# tPen.net
KiCad netlist of a schematic drawn in Altium Designer
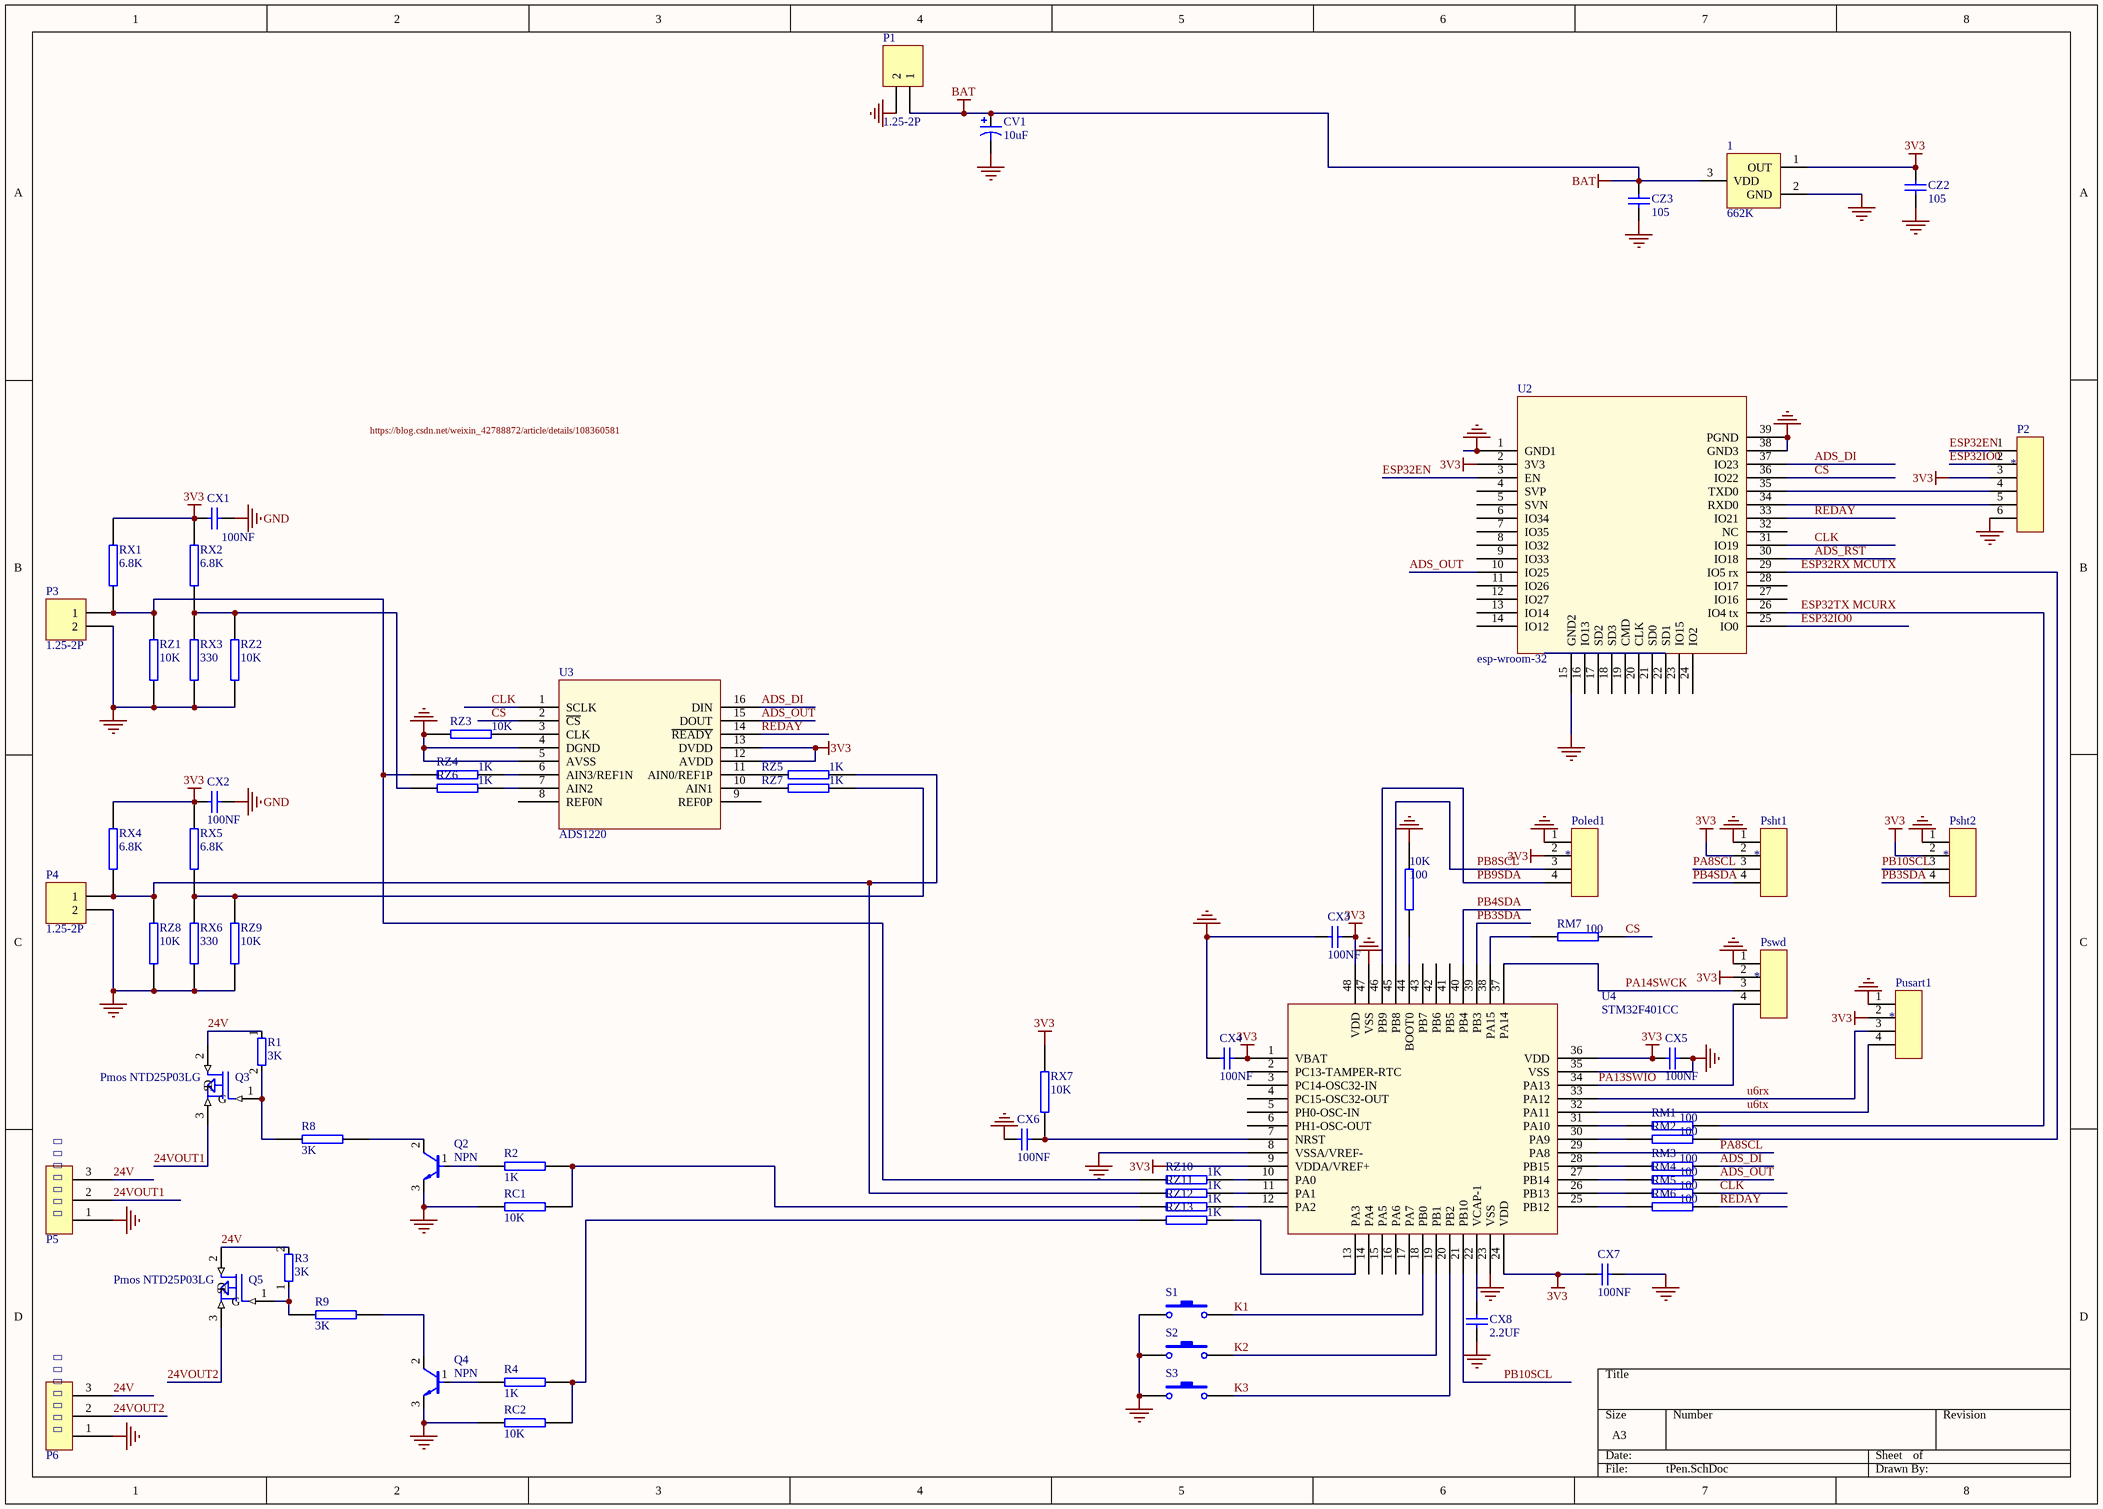
[diagram p0: tPen.SchDoc]

(export (version "E")
  (design (tool "Eeschema 10.0.6"))
  (components
    (comp (ref "1")
      (value "662K")
      (footprint "SOT23-3-1")
      (libsource (lib "SCHÔ­ï¿½ï¿½Í¼ï¿½ï¿½") (part "MH5330"))
    )
    (comp (ref "10K") (value "100") (footprint "0603") (libsource (lib "*") (part "RES2")))
    (comp (ref "CV1")
      (value "10uF")
      (footprint "0603")
      (description "Polarized Capacitor (Radial)")
      (libsource (lib "Miscellaneous Devices") (part "Cap Pol1"))
    )
    (comp (ref "CX1")
      (value "100NF")
      (footprint "0603")
      (description "Capacitor")
      (libsource (lib "Ô­ï¿½ï¿½Í¼ï¿½ï¿½") (part "104"))
    )
    (comp (ref "CX2")
      (value "100NF")
      (footprint "0603")
      (description "Capacitor")
      (libsource (lib "Ô­ï¿½ï¿½Í¼ï¿½ï¿½") (part "104"))
    )
    (comp (ref "CX3")
      (value "100NF")
      (footprint "0603")
      (description "Capacitor")
      (libsource (lib "Ô­ï¿½ï¿½Í¼ï¿½ï¿½") (part "104"))
    )
    (comp (ref "CX4")
      (value "100NF")
      (footprint "0603")
      (description "Capacitor")
      (libsource (lib "Ô­ï¿½ï¿½Í¼ï¿½ï¿½") (part "104"))
    )
    (comp (ref "CX5")
      (value "100NF")
      (footprint "0603")
      (description "Capacitor")
      (libsource (lib "Ô­ï¿½ï¿½Í¼ï¿½ï¿½") (part "104"))
    )
    (comp (ref "CX6")
      (value "100NF")
      (footprint "0603")
      (description "Capacitor")
      (libsource (lib "Ô­ï¿½ï¿½Í¼ï¿½ï¿½") (part "104"))
    )
    (comp (ref "CX7")
      (value "100NF")
      (footprint "0603")
      (description "Capacitor")
      (libsource (lib "Ô­ï¿½ï¿½Í¼ï¿½ï¿½") (part "104"))
    )
    (comp (ref "CX8")
      (value "2.2UF")
      (footprint "0603")
      (description "Capacitor")
      (libsource (lib "Ô­ï¿½ï¿½Í¼ï¿½ï¿½") (part "104"))
    )
    (comp (ref "CZ2")
      (value "105")
      (footprint "0603")
      (description "Capacitor")
      (libsource (lib "Ô­ï¿½ï¿½Í¼ï¿½ï¿½") (part "104"))
    )
    (comp (ref "CZ3")
      (value "105")
      (footprint "0603")
      (description "Capacitor")
      (libsource (lib "Ô­ï¿½ï¿½Í¼ï¿½ï¿½") (part "104"))
    )
    (comp (ref "P1")
      (value "1.25-2P")
      (footprint "1.25ï¿½ï¿½ï¿½ï¿½-ï¿½ï¿½Ê½Í¨ï¿½ï¿½-2P")
      (description "Header, 2-Pin")
      (fields (field (name "PUBLISHER") "Altium Limited"))
      (libsource (lib "") (part "Header 2_1"))
    )
    (comp (ref "P2") (value "*") (footprint "B6B-XH-A") (libsource (lib "") (part "ï¿½Ó²ï¿½ï¿½ï¿½ï¿?P_1")))
    (comp (ref "P3")
      (value "1.25-2P")
      (footprint "1.25ï¿½ï¿½ï¿½ï¿½-ï¿½ï¿½Ê½Í¨ï¿½ï¿½-2P")
      (description "Header, 2-Pin")
      (fields (field (name "PUBLISHER") "Altium Limited"))
      (libsource (lib "SCHÔ­ï¿½ï¿½Í¼ï¿½ï¿½") (part "Header 2"))
    )
    (comp (ref "P4")
      (value "1.25-2P")
      (footprint "1.25ï¿½ï¿½ï¿½ï¿½-ï¿½ï¿½Ê½Í¨ï¿½ï¿½-2P")
      (description "Header, 2-Pin")
      (fields (field (name "PUBLISHER") "Altium Limited"))
      (libsource (lib "SCHÔ­ï¿½ï¿½Í¼ï¿½ï¿½") (part "Header 2"))
    )
    (comp (ref "P5")
      (value "3Pï¿½ï¿½ï¿½ß¶ï¿½ï¿½ï¿½")
      (footprint "XH2.54-3")
      (libsource (lib "ï¿½Ó²ï¿½ï¿½Ôªï¿½ï¿½ï¿½ï¿?SchLib") (part "3Pï¿½ï¿½ï¿½ß¶ï¿½ï¿½ï¿½"))
    )
    (comp (ref "P6")
      (value "3Pï¿½ï¿½ï¿½ß¶ï¿½ï¿½ï¿½")
      (footprint "XH2.54-3")
      (libsource (lib "ï¿½Ó²ï¿½ï¿½Ôªï¿½ï¿½ï¿½ï¿?SchLib") (part "3Pï¿½ï¿½ï¿½ß¶ï¿½ï¿½ï¿½"))
    )
    (comp (ref "Poled1")
      (value "*")
      (footprint "0.96OLED")
      (libsource (lib "ï¿½Ó²ï¿½ï¿½Ôªï¿½ï¿½ï¿½ï¿?SchLib") (part "ï¿½Ó²ï¿½ï¿½ï¿½ï¿?P"))
    )
    (comp (ref "Psht1")
      (value "*")
      (footprint "B4B-XH-A")
      (libsource (lib "ï¿½Ó²ï¿½ï¿½Ôªï¿½ï¿½ï¿½ï¿?SchLib") (part "ï¿½Ó²ï¿½ï¿½ï¿½ï¿?P"))
    )
    (comp (ref "Psht2")
      (value "*")
      (footprint "B4B-XH-A")
      (libsource (lib "ï¿½Ó²ï¿½ï¿½Ôªï¿½ï¿½ï¿½ï¿?SchLib") (part "ï¿½Ó²ï¿½ï¿½ï¿½ï¿?P"))
    )
    (comp (ref "Pswd")
      (value "*")
      (footprint "B4B-XH-A")
      (libsource (lib "ï¿½Ó²ï¿½ï¿½Ôªï¿½ï¿½ï¿½ï¿?SchLib") (part "ï¿½Ó²ï¿½ï¿½ï¿½ï¿?P"))
    )
    (comp (ref "Pusart1")
      (value "*")
      (footprint "B4B-XH-A")
      (libsource (lib "ï¿½Ó²ï¿½ï¿½Ôªï¿½ï¿½ï¿½ï¿?SchLib") (part "ï¿½Ó²ï¿½ï¿½ï¿½ï¿?P"))
    )
    (comp (ref "Q2")
      (value "NPN")
      (footprint "SOT23")
      (libsource (lib "ï¿½ï¿½ï¿½ï¿½Ôªï¿½ï¿½ï¿½ï¿½") (part "NPN"))
    )
    (comp (ref "Q3")
      (value "Pmos NTD25P03LG")
      (libsource (lib "ï¿½ï¿½Ð§Ó¦ï¿½Ü¼ï¿½ï¿½É¿Ø¹ï¿½") (part "MOSFET P"))
    )
    (comp (ref "Q4")
      (value "NPN")
      (footprint "SOT23")
      (libsource (lib "ï¿½ï¿½ï¿½ï¿½Ôªï¿½ï¿½ï¿½ï¿½") (part "NPN"))
    )
    (comp (ref "Q5")
      (value "Pmos NTD25P03LG")
      (libsource (lib "ï¿½ï¿½Ð§Ó¦ï¿½Ü¼ï¿½ï¿½É¿Ø¹ï¿½") (part "MOSFET P"))
    )
    (comp (ref "R1") (value "3K") (footprint "0603") (libsource (lib "*") (part "RES")))
    (comp (ref "R2") (value "1K") (footprint "0603") (libsource (lib "*") (part "RES2")))
    (comp (ref "R3") (value "3K") (footprint "0603") (libsource (lib "*") (part "RES")))
    (comp (ref "R4") (value "1K") (footprint "0603") (libsource (lib "*") (part "RES2")))
    (comp (ref "R8") (value "3K") (footprint "0603") (libsource (lib "*") (part "RES2")))
    (comp (ref "R9") (value "3K") (footprint "0603") (libsource (lib "*") (part "RES2")))
    (comp (ref "RC1") (value "10K") (footprint "0603") (libsource (lib "*") (part "RES2")))
    (comp (ref "RC2") (value "10K") (footprint "0603") (libsource (lib "*") (part "RES2")))
    (comp (ref "RM1") (value "100") (footprint "0603") (libsource (lib "*") (part "RES2")))
    (comp (ref "RM2") (value "100") (footprint "0603") (libsource (lib "*") (part "RES2")))
    (comp (ref "RM3") (value "100") (footprint "0603") (libsource (lib "*") (part "RES2")))
    (comp (ref "RM4") (value "100") (footprint "0603") (libsource (lib "*") (part "RES2")))
    (comp (ref "RM5") (value "100") (footprint "0603") (libsource (lib "*") (part "RES2")))
    (comp (ref "RM6") (value "100") (footprint "0603") (libsource (lib "*") (part "RES2")))
    (comp (ref "RM7") (value "100") (footprint "0603") (libsource (lib "*") (part "RES2")))
    (comp (ref "RX1") (value "6.8K") (footprint "0603") (libsource (lib "*") (part "RES2")))
    (comp (ref "RX2") (value "6.8K") (footprint "0603") (libsource (lib "*") (part "RES2")))
    (comp (ref "RX3") (value "330") (footprint "0603") (libsource (lib "*") (part "RES2")))
    (comp (ref "RX4") (value "6.8K") (footprint "0603") (libsource (lib "*") (part "RES2")))
    (comp (ref "RX5") (value "6.8K") (footprint "0603") (libsource (lib "*") (part "RES2")))
    (comp (ref "RX6") (value "330") (footprint "0603") (libsource (lib "*") (part "RES2")))
    (comp (ref "RX7") (value "10K") (footprint "0603") (libsource (lib "*") (part "RES2")))
    (comp (ref "RZ1") (value "10K") (footprint "0603") (libsource (lib "*") (part "RES2")))
    (comp (ref "RZ2") (value "10K") (footprint "0603") (libsource (lib "*") (part "RES2")))
    (comp (ref "RZ3") (value "10K") (footprint "0603") (libsource (lib "*") (part "RES2")))
    (comp (ref "RZ4") (value "1K") (footprint "0603") (libsource (lib "*") (part "RES2")))
    (comp (ref "RZ5") (value "1K") (footprint "0603") (libsource (lib "*") (part "RES2")))
    (comp (ref "RZ6") (value "1K") (footprint "0603") (libsource (lib "*") (part "RES2")))
    (comp (ref "RZ7") (value "1K") (footprint "0603") (libsource (lib "*") (part "RES2")))
    (comp (ref "RZ8") (value "10K") (footprint "0603") (libsource (lib "*") (part "RES2")))
    (comp (ref "RZ9") (value "10K") (footprint "0603") (libsource (lib "*") (part "RES2")))
    (comp (ref "RZ10") (value "1K") (footprint "0603") (libsource (lib "*") (part "RES2")))
    (comp (ref "RZ11") (value "1K") (footprint "0603") (libsource (lib "*") (part "RES2")))
    (comp (ref "RZ12") (value "1K") (footprint "0603") (libsource (lib "*") (part "RES2")))
    (comp (ref "RZ13") (value "1K") (footprint "0603") (libsource (lib "*") (part "RES2")))
    (comp (ref "S1")
      (value "~")
      (footprint "ï¿½ï¿½Î»ï¿½ï¿½ï¿½ï¿½")
      (libsource (lib "ï¿½ï¿½ï¿½ï¿½_ï¿½ï¿½ï¿½ï¿½Ô­ï¿½ï¿½Í¼ï¿½ï¿½") (part "ï¿½á´¥ï¿½ï¿½ï¿½ï¿½"))
    )
    (comp (ref "S2")
      (value "~")
      (footprint "ï¿½ï¿½Î»ï¿½ï¿½ï¿½ï¿½")
      (libsource (lib "ï¿½ï¿½ï¿½ï¿½_ï¿½ï¿½ï¿½ï¿½Ô­ï¿½ï¿½Í¼ï¿½ï¿½") (part "ï¿½á´¥ï¿½ï¿½ï¿½ï¿½"))
    )
    (comp (ref "S3")
      (value "~")
      (footprint "ï¿½ï¿½Î»ï¿½ï¿½ï¿½ï¿½")
      (libsource (lib "ï¿½ï¿½ï¿½ï¿½_ï¿½ï¿½ï¿½ï¿½Ô­ï¿½ï¿½Í¼ï¿½ï¿½") (part "ï¿½á´¥ï¿½ï¿½ï¿½ï¿½"))
    )
    (comp (ref "U2")
      (value "esp-wroom-32")
      (footprint "ESP32")
      (libsource (lib "STM32F401CC") (part "esp-wroom-32"))
    )
    (comp (ref "U3") (value "ADS1220") (footprint "SSOP16") (libsource (lib "STM32F401CC") (part "ADS1220")))
    (comp (ref "U4")
      (value "STM32F401CC")
      (footprint "STM32F401CC-UFQFPN48")
      (libsource (lib "STM32F401CC") (part "STM32F401CC"))
    )
  )
  (nets
    (net (code "1") (name "/24V") (class "Default")
      (node (ref "P5") (pin "3") (pinfunction "3_3") (pintype "passive"))
      (node (ref "P6") (pin "3") (pinfunction "3_3") (pintype "passive"))
      (node (ref "Q3") (pin "2") (pinfunction "D_2") (pintype "input"))
      (node (ref "Q5") (pin "2") (pinfunction "D_2") (pintype "input"))
      (node (ref "R1") (pin "1") (pinfunction "1_1") (pintype "passive"))
      (node (ref "R3") (pin "2") (pinfunction "2_2") (pintype "passive"))
    )
    (net (code "2") (name "/24VOUT1") (class "Default")
      (node (ref "P5") (pin "2") (pinfunction "2_2") (pintype "passive"))
      (node (ref "Q3") (pin "3") (pinfunction "S_3") (pintype "input"))
    )
    (net (code "3") (name "/24VOUT2") (class "Default")
      (node (ref "P6") (pin "2") (pinfunction "2_2") (pintype "passive"))
      (node (ref "Q5") (pin "3") (pinfunction "S_3") (pintype "input"))
    )
    (net (code "4") (name "/ADS_DI") (class "Default")
      (node (ref "RM3") (pin "2") (pinfunction "2_2") (pintype "passive"))
      (node (ref "U2") (pin "37") (pinfunction "IO23_37") (pintype "passive"))
      (node (ref "U3") (pin "16") (pinfunction "DIN_16") (pintype "passive"))
    )
    (net (code "5") (name "/ADS_OUT") (class "Default")
      (node (ref "RM4") (pin "2") (pinfunction "2_2") (pintype "passive"))
      (node (ref "U2") (pin "10") (pinfunction "IO25_10") (pintype "passive"))
      (node (ref "U3") (pin "15") (pinfunction "DOUT_15") (pintype "passive"))
    )
    (net (code "6") (name "/ADS_RST") (class "Default")
      (node (ref "U2") (pin "30") (pinfunction "IO18_30") (pintype "passive"))
    )
    (net (code "7") (name "/CLK") (class "Default")
      (node (ref "RM5") (pin "2") (pinfunction "2_2") (pintype "passive"))
      (node (ref "U2") (pin "31") (pinfunction "IO19_31") (pintype "passive"))
      (node (ref "U3") (pin "1") (pinfunction "SCLK_1") (pintype "passive"))
    )
    (net (code "8") (name "/CS") (class "Default")
      (node (ref "RM7") (pin "2") (pinfunction "2_2") (pintype "passive"))
      (node (ref "U2") (pin "36") (pinfunction "IO22_36") (pintype "passive"))
      (node (ref "U3") (pin "2") (pinfunction "~{CS}_2") (pintype "passive"))
    )
    (net (code "9") (name "/ESP32EN") (class "Default")
      (node (ref "P2") (pin "1") (pinfunction "1_1") (pintype "passive"))
      (node (ref "U2") (pin "3") (pinfunction "EN_3") (pintype "passive"))
    )
    (net (code "10") (name "/ESP32IO0") (class "Default")
      (node (ref "P2") (pin "2") (pinfunction "2_2") (pintype "passive"))
      (node (ref "U2") (pin "25") (pinfunction "IO0_25") (pintype "passive"))
    )
    (net (code "11") (name "/ESP32RX MCUTX") (class "Default")
      (node (ref "RM2") (pin "2") (pinfunction "2_2") (pintype "passive"))
      (node (ref "U2") (pin "29") (pinfunction "IO5_rx_29") (pintype "passive"))
    )
    (net (code "12") (name "/ESP32TX MCURX") (class "Default")
      (node (ref "RM1") (pin "2") (pinfunction "2_2") (pintype "passive"))
      (node (ref "U2") (pin "26") (pinfunction "IO4_tx_26") (pintype "passive"))
    )
    (net (code "13") (name "/K1") (class "Default")
      (node (ref "S1") (pin "2") (pinfunction "2_2") (pintype "passive"))
      (node (ref "U4") (pin "18") (pinfunction "PB0_18") (pintype "passive"))
    )
    (net (code "14") (name "/K2") (class "Default")
      (node (ref "S2") (pin "2") (pinfunction "2_2") (pintype "passive"))
      (node (ref "U4") (pin "19") (pinfunction "PB1_19") (pintype "passive"))
    )
    (net (code "15") (name "/K3") (class "Default")
      (node (ref "S3") (pin "2") (pinfunction "2_2") (pintype "passive"))
      (node (ref "U4") (pin "20") (pinfunction "PB2_20") (pintype "passive"))
    )
    (net (code "16") (name "/PA8SCL") (class "Default")
      (node (ref "Psht1") (pin "3") (pinfunction "3_3") (pintype "passive"))
      (node (ref "U4") (pin "29") (pinfunction "PA8_29") (pintype "passive"))
    )
    (net (code "17") (name "/PA13SWIO") (class "Default")
      (node (ref "Pswd") (pin "4") (pinfunction "4_4") (pintype "passive"))
      (node (ref "U4") (pin "34") (pinfunction "PA13_34") (pintype "passive"))
    )
    (net (code "18") (name "/PA14SWCK") (class "Default")
      (node (ref "Pswd") (pin "3") (pinfunction "3_3") (pintype "passive"))
      (node (ref "U4") (pin "37") (pinfunction "PA14_37") (pintype "passive"))
    )
    (net (code "19") (name "/PB3SDA") (class "Default")
      (node (ref "Psht2") (pin "4") (pinfunction "4_4") (pintype "passive"))
      (node (ref "U4") (pin "39") (pinfunction "PB3_39") (pintype "passive"))
    )
    (net (code "20") (name "/PB4SDA") (class "Default")
      (node (ref "Psht1") (pin "4") (pinfunction "4_4") (pintype "passive"))
      (node (ref "U4") (pin "40") (pinfunction "PB4_40") (pintype "passive"))
    )
    (net (code "21") (name "/PB8SCL") (class "Default")
      (node (ref "Poled1") (pin "3") (pinfunction "3_3") (pintype "passive"))
      (node (ref "U4") (pin "45") (pinfunction "PB8_45") (pintype "passive"))
    )
    (net (code "22") (name "/PB9SDA") (class "Default")
      (node (ref "Poled1") (pin "4") (pinfunction "4_4") (pintype "passive"))
      (node (ref "U4") (pin "46") (pinfunction "PB9_46") (pintype "passive"))
    )
    (net (code "23") (name "/PB10SCL") (class "Default")
      (node (ref "Psht2") (pin "3") (pinfunction "3_3") (pintype "passive"))
      (node (ref "U4") (pin "21") (pinfunction "PB10_21") (pintype "passive"))
    )
    (net (code "24") (name "/REDAY") (class "Default")
      (node (ref "RM6") (pin "2") (pinfunction "2_2") (pintype "passive"))
      (node (ref "U2") (pin "33") (pinfunction "IO21_33") (pintype "passive"))
      (node (ref "U3") (pin "14") (pinfunction "~{READY}_14") (pintype "passive"))
    )
    (net (code "26") (name "/u6rx") (class "Default")
      (node (ref "Pusart1") (pin "3") (pinfunction "3_3") (pintype "passive"))
      (node (ref "U4") (pin "33") (pinfunction "PA12_33") (pintype "passive"))
    )
    (net (code "27") (name "/u6tx") (class "Default")
      (node (ref "Pusart1") (pin "4") (pinfunction "4_4") (pintype "passive"))
      (node (ref "U4") (pin "32") (pinfunction "PA11_32") (pintype "passive"))
    )
    (net (code "28") (name "3V3") (class "Default")
      (node (ref "1") (pin "1") (pinfunction "OUT_1") (pintype "passive"))
      (node (ref "CX1") (pin "1") (pinfunction "1_1") (pintype "passive"))
      (node (ref "CX2") (pin "1") (pinfunction "1_1") (pintype "passive"))
      (node (ref "CX3") (pin "2") (pinfunction "2_2") (pintype "passive"))
      (node (ref "CX4") (pin "2") (pinfunction "2_2") (pintype "passive"))
      (node (ref "CX5") (pin "1") (pinfunction "1_1") (pintype "passive"))
      (node (ref "CX7") (pin "1") (pinfunction "1_1") (pintype "passive"))
      (node (ref "CZ2") (pin "1") (pinfunction "1_1") (pintype "passive"))
      (node (ref "P2") (pin "3") (pinfunction "3_3") (pintype "passive"))
      (node (ref "Poled1") (pin "2") (pinfunction "2_2") (pintype "passive"))
      (node (ref "Psht1") (pin "2") (pinfunction "2_2") (pintype "passive"))
      (node (ref "Psht2") (pin "2") (pinfunction "2_2") (pintype "passive"))
      (node (ref "Pswd") (pin "2") (pinfunction "2_2") (pintype "passive"))
      (node (ref "Pusart1") (pin "2") (pinfunction "2_2") (pintype "passive"))
      (node (ref "RX1") (pin "1") (pinfunction "1_1") (pintype "passive"))
      (node (ref "RX2") (pin "1") (pinfunction "1_1") (pintype "passive"))
      (node (ref "RX4") (pin "1") (pinfunction "1_1") (pintype "passive"))
      (node (ref "RX5") (pin "1") (pinfunction "1_1") (pintype "passive"))
      (node (ref "RX7") (pin "2") (pinfunction "2_2") (pintype "passive"))
      (node (ref "U2") (pin "2") (pinfunction "3V3_2") (pintype "passive"))
      (node (ref "U3") (pin "12") (pinfunction "AVDD_12") (pintype "passive"))
      (node (ref "U3") (pin "13") (pinfunction "DVDD_13") (pintype "passive"))
      (node (ref "U4") (pin "1") (pinfunction "VBAT_1") (pintype "passive"))
      (node (ref "U4") (pin "24") (pinfunction "VDD_24") (pintype "passive"))
      (node (ref "U4") (pin "36") (pinfunction "VDD_36") (pintype "passive"))
      (node (ref "U4") (pin "48") (pinfunction "VDD_48") (pintype "passive"))
      (node (ref "U4") (pin "9") (pinfunction "VDDA/VREF+_9") (pintype "passive"))
    )
    (net (code "29") (name "BAT") (class "Default")
      (node (ref "1") (pin "3") (pinfunction "VDD_3") (pintype "passive"))
      (node (ref "CV1") (pin "1") (pinfunction "1_1") (pintype "passive"))
      (node (ref "CZ3") (pin "1") (pinfunction "1_1") (pintype "passive"))
      (node (ref "P1") (pin "1") (pinfunction "1_1") (pintype "passive"))
    )
    (net (code "30") (name "GND") (class "Default")
      (node (ref "1") (pin "2") (pinfunction "GND_2") (pintype "passive"))
      (node (ref "10K") (pin "2") (pinfunction "2_2") (pintype "passive"))
      (node (ref "CV1") (pin "2") (pinfunction "2_2") (pintype "passive"))
      (node (ref "CX1") (pin "2") (pinfunction "2_2") (pintype "passive"))
      (node (ref "CX2") (pin "2") (pinfunction "2_2") (pintype "passive"))
      (node (ref "CX3") (pin "1") (pinfunction "1_1") (pintype "passive"))
      (node (ref "CX4") (pin "1") (pinfunction "1_1") (pintype "passive"))
      (node (ref "CX5") (pin "2") (pinfunction "2_2") (pintype "passive"))
      (node (ref "CX6") (pin "2") (pinfunction "2_2") (pintype "passive"))
      (node (ref "CX7") (pin "2") (pinfunction "2_2") (pintype "passive"))
      (node (ref "CX8") (pin "2") (pinfunction "2_2") (pintype "passive"))
      (node (ref "CZ2") (pin "2") (pinfunction "2_2") (pintype "passive"))
      (node (ref "CZ3") (pin "2") (pinfunction "2_2") (pintype "passive"))
      (node (ref "P1") (pin "2") (pinfunction "2_2") (pintype "passive"))
      (node (ref "P2") (pin "6") (pinfunction "6_6") (pintype "passive"))
      (node (ref "P3") (pin "2") (pinfunction "2_2") (pintype "passive"))
      (node (ref "P4") (pin "2") (pinfunction "2_2") (pintype "passive"))
      (node (ref "P5") (pin "1") (pinfunction "1_1") (pintype "passive"))
      (node (ref "P6") (pin "1") (pinfunction "1_1") (pintype "passive"))
      (node (ref "Poled1") (pin "1") (pinfunction "1_1") (pintype "passive"))
      (node (ref "Psht1") (pin "1") (pinfunction "1_1") (pintype "passive"))
      (node (ref "Psht2") (pin "1") (pinfunction "1_1") (pintype "passive"))
      (node (ref "Pswd") (pin "1") (pinfunction "1_1") (pintype "passive"))
      (node (ref "Pusart1") (pin "1") (pinfunction "1_1") (pintype "passive"))
      (node (ref "Q2") (pin "3") (pinfunction "3e_3") (pintype "passive"))
      (node (ref "Q4") (pin "3") (pinfunction "3e_3") (pintype "passive"))
      (node (ref "RC1") (pin "1") (pinfunction "1_1") (pintype "passive"))
      (node (ref "RC2") (pin "1") (pinfunction "1_1") (pintype "passive"))
      (node (ref "RX3") (pin "2") (pinfunction "2_2") (pintype "passive"))
      (node (ref "RX6") (pin "2") (pinfunction "2_2") (pintype "passive"))
      (node (ref "RZ1") (pin "2") (pinfunction "2_2") (pintype "passive"))
      (node (ref "RZ2") (pin "2") (pinfunction "2_2") (pintype "passive"))
      (node (ref "RZ3") (pin "1") (pinfunction "1_1") (pintype "passive"))
      (node (ref "RZ8") (pin "2") (pinfunction "2_2") (pintype "passive"))
      (node (ref "RZ9") (pin "2") (pinfunction "2_2") (pintype "passive"))
      (node (ref "S1") (pin "1") (pinfunction "1_1") (pintype "passive"))
      (node (ref "S2") (pin "1") (pinfunction "1_1") (pintype "passive"))
      (node (ref "S3") (pin "1") (pinfunction "1_1") (pintype "passive"))
      (node (ref "U2") (pin "1") (pinfunction "GND1_1") (pintype "passive"))
      (node (ref "U2") (pin "15") (pinfunction "GND2_15") (pintype "passive"))
      (node (ref "U2") (pin "38") (pinfunction "GND3_38") (pintype "passive"))
      (node (ref "U2") (pin "39") (pinfunction "PGND_39") (pintype "passive"))
      (node (ref "U3") (pin "4") (pinfunction "DGND_4") (pintype "passive"))
      (node (ref "U3") (pin "5") (pinfunction "AVSS_5") (pintype "passive"))
      (node (ref "U4") (pin "23") (pinfunction "VSS_23") (pintype "passive"))
      (node (ref "U4") (pin "35") (pinfunction "VSS_35") (pintype "passive"))
      (node (ref "U4") (pin "47") (pinfunction "VSS_47") (pintype "passive"))
      (node (ref "U4") (pin "8") (pinfunction "VSSA/VREF-_8") (pintype "passive"))
    )
    (net (code "31") (name "Net-(P3-Pad1)") (class "Default")
      (node (ref "P3") (pin "1") (pinfunction "1_1") (pintype "passive"))
      (node (ref "RX1") (pin "2") (pinfunction "2_2") (pintype "passive"))
      (node (ref "RZ1") (pin "1") (pinfunction "1_1") (pintype "passive"))
      (node (ref "RZ10") (pin "1") (pinfunction "1_1") (pintype "passive"))
      (node (ref "RZ4") (pin "1") (pinfunction "1_1") (pintype "passive"))
    )
    (net (code "32") (name "Net-(P4-Pad1)") (class "Default")
      (node (ref "P4") (pin "1") (pinfunction "1_1") (pintype "passive"))
      (node (ref "RX4") (pin "2") (pinfunction "2_2") (pintype "passive"))
      (node (ref "RZ11") (pin "1") (pinfunction "1_1") (pintype "passive"))
      (node (ref "RZ5") (pin "2") (pinfunction "2_2") (pintype "passive"))
      (node (ref "RZ8") (pin "1") (pinfunction "1_1") (pintype "passive"))
    )
    (net (code "33") (name "Net-(Q2-1b)") (class "Default")
      (node (ref "Q2") (pin "1") (pinfunction "1b_1") (pintype "passive"))
      (node (ref "R2") (pin "1") (pinfunction "1_1") (pintype "passive"))
    )
    (net (code "34") (name "Net-(Q2-2c)") (class "Default")
      (node (ref "Q2") (pin "2") (pinfunction "2c_2") (pintype "passive"))
      (node (ref "R8") (pin "2") (pinfunction "2_2") (pintype "passive"))
    )
    (net (code "35") (name "Net-(Q3-G)") (class "Default")
      (node (ref "Q3") (pin "1") (pinfunction "G_1") (pintype "input"))
      (node (ref "R1") (pin "2") (pinfunction "2_2") (pintype "passive"))
      (node (ref "R8") (pin "1") (pinfunction "1_1") (pintype "passive"))
    )
    (net (code "36") (name "Net-(Q4-1b)") (class "Default")
      (node (ref "Q4") (pin "1") (pinfunction "1b_1") (pintype "passive"))
      (node (ref "R4") (pin "1") (pinfunction "1_1") (pintype "passive"))
    )
    (net (code "37") (name "Net-(Q4-2c)") (class "Default")
      (node (ref "Q4") (pin "2") (pinfunction "2c_2") (pintype "passive"))
      (node (ref "R9") (pin "2") (pinfunction "2_2") (pintype "passive"))
    )
    (net (code "38") (name "Net-(Q5-G)") (class "Default")
      (node (ref "Q5") (pin "1") (pinfunction "G_1") (pintype "input"))
      (node (ref "R3") (pin "1") (pinfunction "1_1") (pintype "passive"))
      (node (ref "R9") (pin "1") (pinfunction "1_1") (pintype "passive"))
    )
    (net (code "39") (name "Net-(R2-Pad2)") (class "Default")
      (node (ref "R2") (pin "2") (pinfunction "2_2") (pintype "passive"))
      (node (ref "RC1") (pin "2") (pinfunction "2_2") (pintype "passive"))
      (node (ref "RZ12") (pin "1") (pinfunction "1_1") (pintype "passive"))
    )
    (net (code "40") (name "Net-(R4-Pad2)") (class "Default")
      (node (ref "R4") (pin "2") (pinfunction "2_2") (pintype "passive"))
      (node (ref "RC2") (pin "2") (pinfunction "2_2") (pintype "passive"))
      (node (ref "RZ13") (pin "1") (pinfunction "1_1") (pintype "passive"))
    )
    (net (code "41") (name "Net-(RX2-Pad2)") (class "Default")
      (node (ref "RX2") (pin "2") (pinfunction "2_2") (pintype "passive"))
      (node (ref "RX3") (pin "1") (pinfunction "1_1") (pintype "passive"))
      (node (ref "RZ2") (pin "1") (pinfunction "1_1") (pintype "passive"))
      (node (ref "RZ6") (pin "1") (pinfunction "1_1") (pintype "passive"))
    )
    (net (code "42") (name "Net-(RX5-Pad2)") (class "Default")
      (node (ref "RX5") (pin "2") (pinfunction "2_2") (pintype "passive"))
      (node (ref "RX6") (pin "1") (pinfunction "1_1") (pintype "passive"))
      (node (ref "RZ7") (pin "2") (pinfunction "2_2") (pintype "passive"))
      (node (ref "RZ9") (pin "1") (pinfunction "1_1") (pintype "passive"))
    )
    (net (code "43") (name "Net-(U2-RXD0)") (class "Default")
      (node (ref "P2") (pin "5") (pinfunction "5_5") (pintype "passive"))
      (node (ref "U2") (pin "34") (pinfunction "RXD0_34") (pintype "passive"))
    )
    (net (code "44") (name "Net-(U2-TXD0)") (class "Default")
      (node (ref "P2") (pin "4") (pinfunction "4_4") (pintype "passive"))
      (node (ref "U2") (pin "35") (pinfunction "TXD0_35") (pintype "passive"))
    )
    (net (code "45") (name "Net-(U3-AIN0{slash}REF1P)") (class "Default")
      (node (ref "RZ5") (pin "1") (pinfunction "1_1") (pintype "passive"))
      (node (ref "U3") (pin "11") (pinfunction "AIN0/REF1P_11") (pintype "passive"))
    )
    (net (code "46") (name "Net-(U3-AIN1)") (class "Default")
      (node (ref "RZ7") (pin "1") (pinfunction "1_1") (pintype "passive"))
      (node (ref "U3") (pin "10") (pinfunction "AIN1_10") (pintype "passive"))
    )
    (net (code "47") (name "Net-(U3-AIN2)") (class "Default")
      (node (ref "RZ6") (pin "2") (pinfunction "2_2") (pintype "passive"))
      (node (ref "U3") (pin "7") (pinfunction "AIN2_7") (pintype "passive"))
    )
    (net (code "48") (name "Net-(U3-AIN3{slash}REF1N)") (class "Default")
      (node (ref "RZ4") (pin "2") (pinfunction "2_2") (pintype "passive"))
      (node (ref "U3") (pin "6") (pinfunction "AIN3/REF1N_6") (pintype "passive"))
    )
    (net (code "49") (name "Net-(U3-CLK)") (class "Default")
      (node (ref "RZ3") (pin "2") (pinfunction "2_2") (pintype "passive"))
      (node (ref "U3") (pin "3") (pinfunction "CLK_3") (pintype "passive"))
    )
    (net (code "50") (name "Net-(U4-BOOT0)") (class "Default")
      (node (ref "10K") (pin "1") (pinfunction "1_1") (pintype "passive"))
      (node (ref "U4") (pin "44") (pinfunction "BOOT0_44") (pintype "passive"))
    )
    (net (code "51") (name "Net-(U4-NRST)") (class "Default")
      (node (ref "CX6") (pin "1") (pinfunction "1_1") (pintype "passive"))
      (node (ref "RX7") (pin "1") (pinfunction "1_1") (pintype "passive"))
      (node (ref "U4") (pin "7") (pinfunction "NRST_7") (pintype "passive"))
    )
    (net (code "52") (name "Net-(U4-PA0)") (class "Default")
      (node (ref "RZ10") (pin "2") (pinfunction "2_2") (pintype "passive"))
      (node (ref "U4") (pin "10") (pinfunction "PA0_10") (pintype "passive"))
    )
    (net (code "53") (name "Net-(U4-PA1)") (class "Default")
      (node (ref "RZ11") (pin "2") (pinfunction "2_2") (pintype "passive"))
      (node (ref "U4") (pin "11") (pinfunction "PA1_11") (pintype "passive"))
    )
    (net (code "54") (name "Net-(U4-PA2)") (class "Default")
      (node (ref "RZ12") (pin "2") (pinfunction "2_2") (pintype "passive"))
      (node (ref "U4") (pin "12") (pinfunction "PA2_12") (pintype "passive"))
    )
    (net (code "55") (name "Net-(U4-PA3)") (class "Default")
      (node (ref "RZ13") (pin "2") (pinfunction "2_2") (pintype "passive"))
      (node (ref "U4") (pin "13") (pinfunction "PA3_13") (pintype "passive"))
    )
    (net (code "56") (name "Net-(U4-PA9)") (class "Default")
      (node (ref "RM2") (pin "1") (pinfunction "1_1") (pintype "passive"))
      (node (ref "U4") (pin "30") (pinfunction "PA9_30") (pintype "passive"))
    )
    (net (code "57") (name "Net-(U4-PA10)") (class "Default")
      (node (ref "RM1") (pin "1") (pinfunction "1_1") (pintype "passive"))
      (node (ref "U4") (pin "31") (pinfunction "PA10_31") (pintype "passive"))
    )
    (net (code "58") (name "Net-(U4-PA15)") (class "Default")
      (node (ref "RM7") (pin "1") (pinfunction "1_1") (pintype "passive"))
      (node (ref "U4") (pin "38") (pinfunction "PA15_38") (pintype "passive"))
    )
    (net (code "59") (name "Net-(U4-PB12)") (class "Default")
      (node (ref "RM6") (pin "1") (pinfunction "1_1") (pintype "passive"))
      (node (ref "U4") (pin "25") (pinfunction "PB12_25") (pintype "passive"))
    )
    (net (code "60") (name "Net-(U4-PB13)") (class "Default")
      (node (ref "RM5") (pin "1") (pinfunction "1_1") (pintype "passive"))
      (node (ref "U4") (pin "26") (pinfunction "PB13_26") (pintype "passive"))
    )
    (net (code "61") (name "Net-(U4-PB14)") (class "Default")
      (node (ref "RM4") (pin "1") (pinfunction "1_1") (pintype "passive"))
      (node (ref "U4") (pin "27") (pinfunction "PB14_27") (pintype "passive"))
    )
    (net (code "62") (name "Net-(U4-PB15)") (class "Default")
      (node (ref "RM3") (pin "1") (pinfunction "1_1") (pintype "passive"))
      (node (ref "U4") (pin "28") (pinfunction "PB15_28") (pintype "passive"))
    )
    (net (code "63") (name "Net-(U4-VCAP-1)") (class "Default")
      (node (ref "CX8") (pin "1") (pinfunction "1_1") (pintype "passive"))
      (node (ref "U4") (pin "22") (pinfunction "VCAP-1_22") (pintype "passive"))
    )
    (net (code "64") (name "unconnected-(U2-CLK-Pad20)") (class "Default")
      (node (ref "U2") (pin "20") (pinfunction "CLK_20") (pintype "passive"))
    )
    (net (code "65") (name "unconnected-(U2-CMD-Pad19)") (class "Default")
      (node (ref "U2") (pin "19") (pinfunction "CMD_19") (pintype "passive"))
    )
    (net (code "66") (name "unconnected-(U2-IO2-Pad24)") (class "Default")
      (node (ref "U2") (pin "24") (pinfunction "IO2_24") (pintype "passive"))
    )
    (net (code "67") (name "unconnected-(U2-IO12-Pad14)") (class "Default")
      (node (ref "U2") (pin "14") (pinfunction "IO12_14") (pintype "passive"))
    )
    (net (code "68") (name "unconnected-(U2-IO13-Pad16)") (class "Default")
      (node (ref "U2") (pin "16") (pinfunction "IO13_16") (pintype "passive"))
    )
    (net (code "69") (name "unconnected-(U2-IO14-Pad13)") (class "Default")
      (node (ref "U2") (pin "13") (pinfunction "IO14_13") (pintype "passive"))
    )
    (net (code "70") (name "unconnected-(U2-IO15-Pad23)") (class "Default")
      (node (ref "U2") (pin "23") (pinfunction "IO15_23") (pintype "passive"))
    )
    (net (code "71") (name "unconnected-(U2-IO16-Pad27)") (class "Default")
      (node (ref "U2") (pin "27") (pinfunction "IO16_27") (pintype "passive"))
    )
    (net (code "72") (name "unconnected-(U2-IO17-Pad28)") (class "Default")
      (node (ref "U2") (pin "28") (pinfunction "IO17_28") (pintype "passive"))
    )
    (net (code "73") (name "unconnected-(U2-IO26-Pad11)") (class "Default")
      (node (ref "U2") (pin "11") (pinfunction "IO26_11") (pintype "passive"))
    )
    (net (code "74") (name "unconnected-(U2-IO27-Pad12)") (class "Default")
      (node (ref "U2") (pin "12") (pinfunction "IO27_12") (pintype "passive"))
    )
    (net (code "75") (name "unconnected-(U2-IO32-Pad8)") (class "Default")
      (node (ref "U2") (pin "8") (pinfunction "IO32_8") (pintype "passive"))
    )
    (net (code "76") (name "unconnected-(U2-IO33-Pad9)") (class "Default")
      (node (ref "U2") (pin "9") (pinfunction "IO33_9") (pintype "passive"))
    )
    (net (code "77") (name "unconnected-(U2-IO34-Pad6)") (class "Default")
      (node (ref "U2") (pin "6") (pinfunction "IO34_6") (pintype "passive"))
    )
    (net (code "78") (name "unconnected-(U2-IO35-Pad7)") (class "Default")
      (node (ref "U2") (pin "7") (pinfunction "IO35_7") (pintype "passive"))
    )
    (net (code "79") (name "unconnected-(U2-NC-Pad32)") (class "Default")
      (node (ref "U2") (pin "32") (pinfunction "NC_32") (pintype "passive"))
    )
    (net (code "80") (name "unconnected-(U2-SD0-Pad21)") (class "Default")
      (node (ref "U2") (pin "21") (pinfunction "SD0_21") (pintype "passive"))
    )
    (net (code "81") (name "unconnected-(U2-SD1-Pad22)") (class "Default")
      (node (ref "U2") (pin "22") (pinfunction "SD1_22") (pintype "passive"))
    )
    (net (code "82") (name "unconnected-(U2-SD2-Pad17)") (class "Default")
      (node (ref "U2") (pin "17") (pinfunction "SD2_17") (pintype "passive"))
    )
    (net (code "83") (name "unconnected-(U2-SD3-Pad18)") (class "Default")
      (node (ref "U2") (pin "18") (pinfunction "SD3_18") (pintype "passive"))
    )
    (net (code "84") (name "unconnected-(U2-SVN-Pad5)") (class "Default")
      (node (ref "U2") (pin "5") (pinfunction "SVN_5") (pintype "passive"))
    )
    (net (code "85") (name "unconnected-(U2-SVP-Pad4)") (class "Default")
      (node (ref "U2") (pin "4") (pinfunction "SVP_4") (pintype "passive"))
    )
    (net (code "86") (name "unconnected-(U3-REF0N-Pad8)") (class "Default")
      (node (ref "U3") (pin "8") (pinfunction "REF0N_8") (pintype "passive"))
    )
    (net (code "87") (name "unconnected-(U3-REF0P-Pad9)") (class "Default")
      (node (ref "U3") (pin "9") (pinfunction "REF0P_9") (pintype "passive"))
    )
    (net (code "88") (name "unconnected-(U4-PA4-Pad14)") (class "Default")
      (node (ref "U4") (pin "14") (pinfunction "PA4_14") (pintype "passive"))
    )
    (net (code "89") (name "unconnected-(U4-PA5-Pad15)") (class "Default")
      (node (ref "U4") (pin "15") (pinfunction "PA5_15") (pintype "passive"))
    )
    (net (code "90") (name "unconnected-(U4-PA6-Pad16)") (class "Default")
      (node (ref "U4") (pin "16") (pinfunction "PA6_16") (pintype "passive"))
    )
    (net (code "91") (name "unconnected-(U4-PA7-Pad17)") (class "Default")
      (node (ref "U4") (pin "17") (pinfunction "PA7_17") (pintype "passive"))
    )
    (net (code "92") (name "unconnected-(U4-PB5-Pad41)") (class "Default")
      (node (ref "U4") (pin "41") (pinfunction "PB5_41") (pintype "passive"))
    )
    (net (code "93") (name "unconnected-(U4-PB6-Pad42)") (class "Default")
      (node (ref "U4") (pin "42") (pinfunction "PB6_42") (pintype "passive"))
    )
    (net (code "94") (name "unconnected-(U4-PB7-Pad43)") (class "Default")
      (node (ref "U4") (pin "43") (pinfunction "PB7_43") (pintype "passive"))
    )
    (net (code "95") (name "unconnected-(U4-PC13-TAMPER-RTC-Pad2)") (class "Default")
      (node (ref "U4") (pin "2") (pinfunction "PC13-TAMPER-RTC_2") (pintype "passive"))
    )
    (net (code "96") (name "unconnected-(U4-PC14-OSC32-IN-Pad3)") (class "Default")
      (node (ref "U4") (pin "3") (pinfunction "PC14-OSC32-IN_3") (pintype "passive"))
    )
    (net (code "97") (name "unconnected-(U4-PC15-OSC32-OUT-Pad4)") (class "Default")
      (node (ref "U4") (pin "4") (pinfunction "PC15-OSC32-OUT_4") (pintype "passive"))
    )
    (net (code "98") (name "unconnected-(U4-PH0-OSC-IN-Pad5)") (class "Default")
      (node (ref "U4") (pin "5") (pinfunction "PH0-OSC-IN_5") (pintype "passive"))
    )
    (net (code "99") (name "unconnected-(U4-PH1-OSC-OUT-Pad6)") (class "Default")
      (node (ref "U4") (pin "6") (pinfunction "PH1-OSC-OUT_6") (pintype "passive"))
    )
  )
)
